# ME433-2021-1.net
KiCad netlist of a schematic drawn in EAGLE
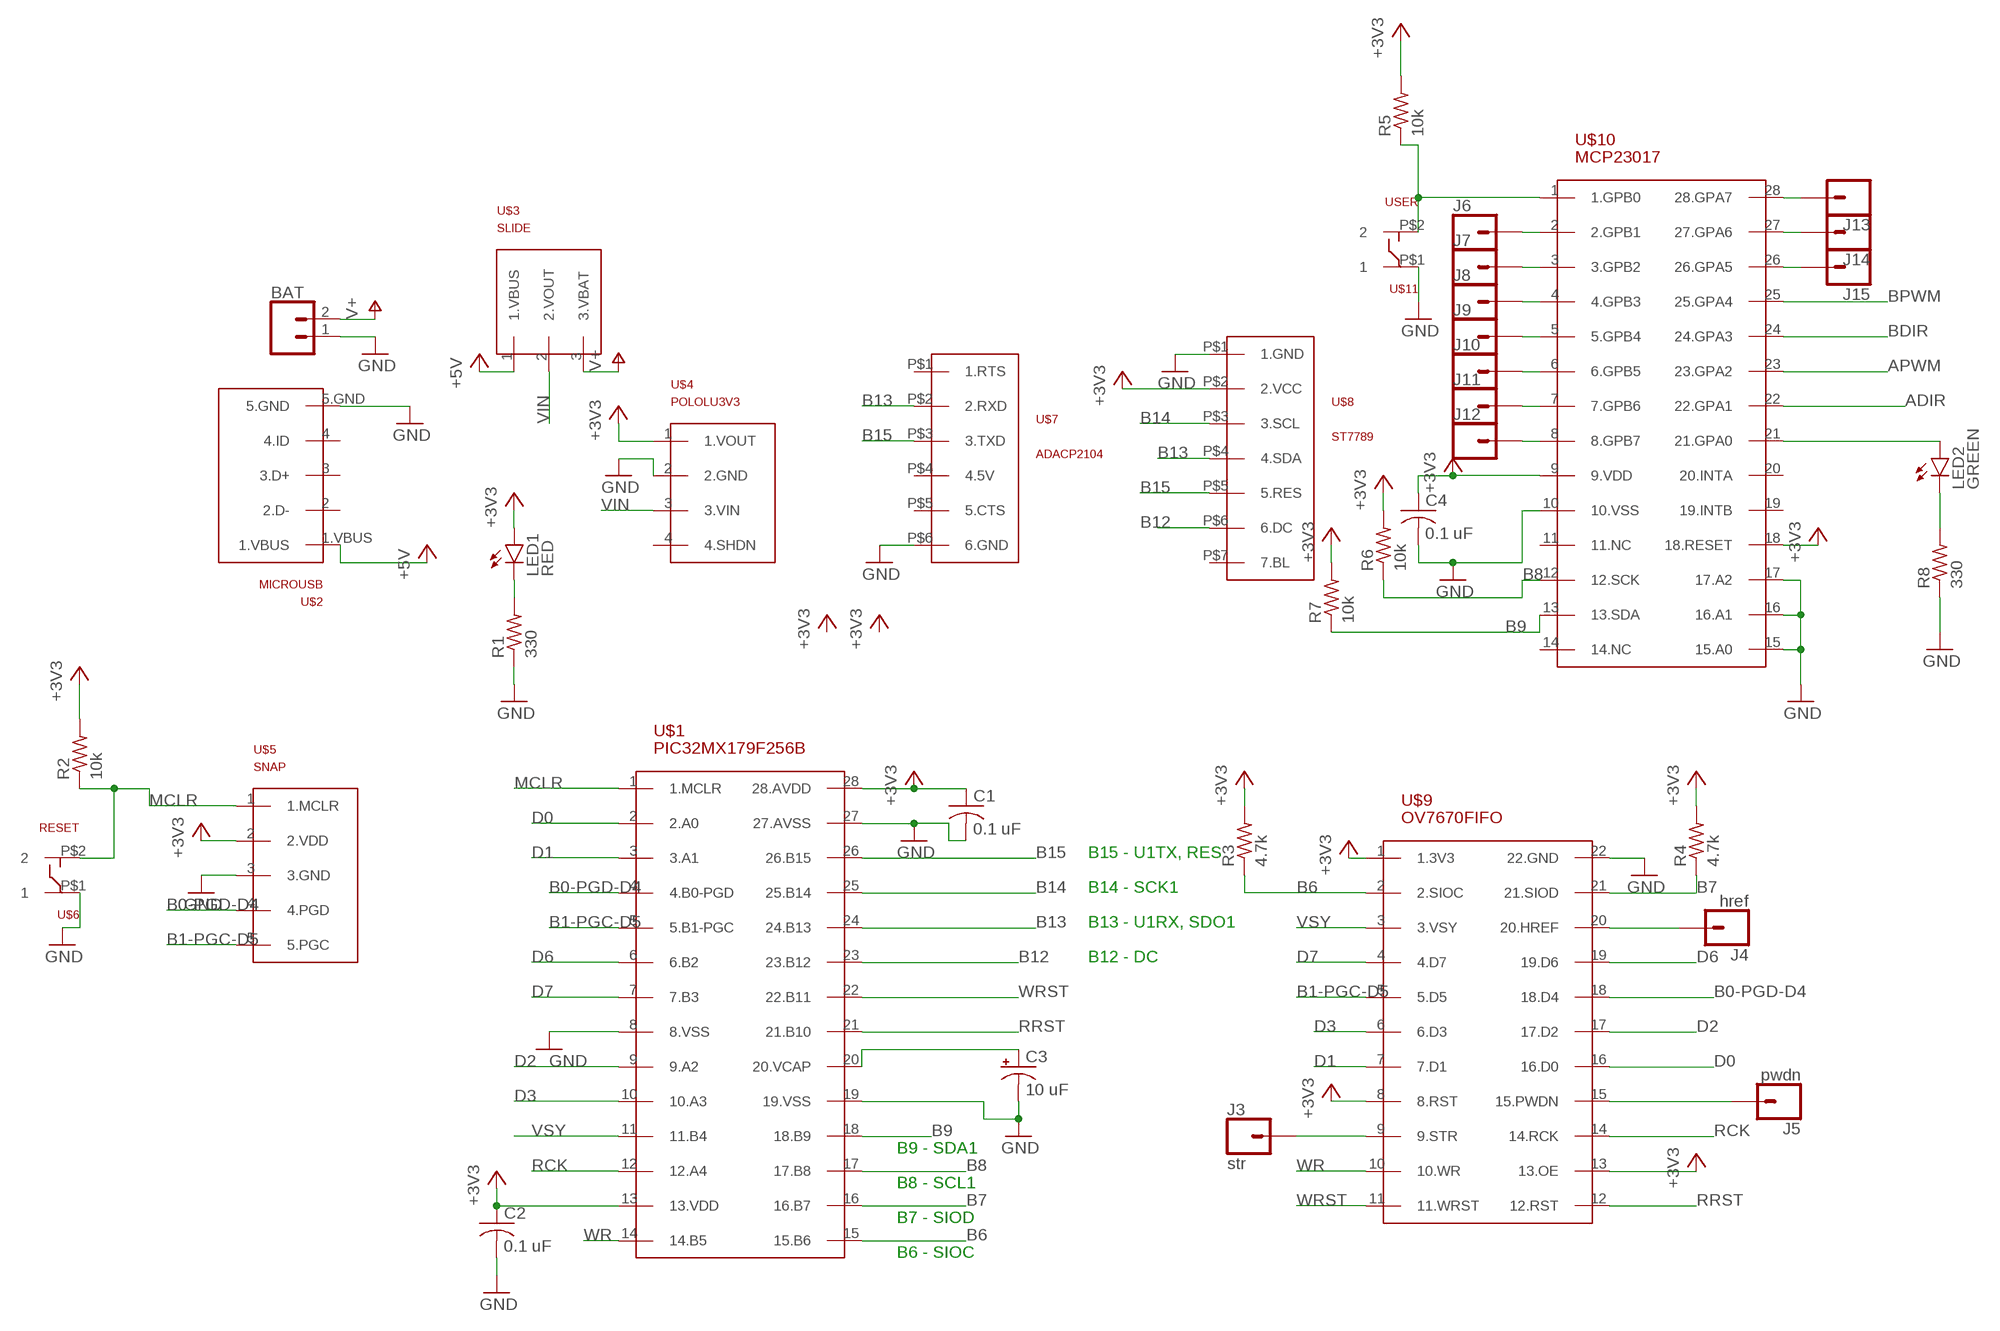
[diagram p0: schematic, sheet 1, part 1 of 2]
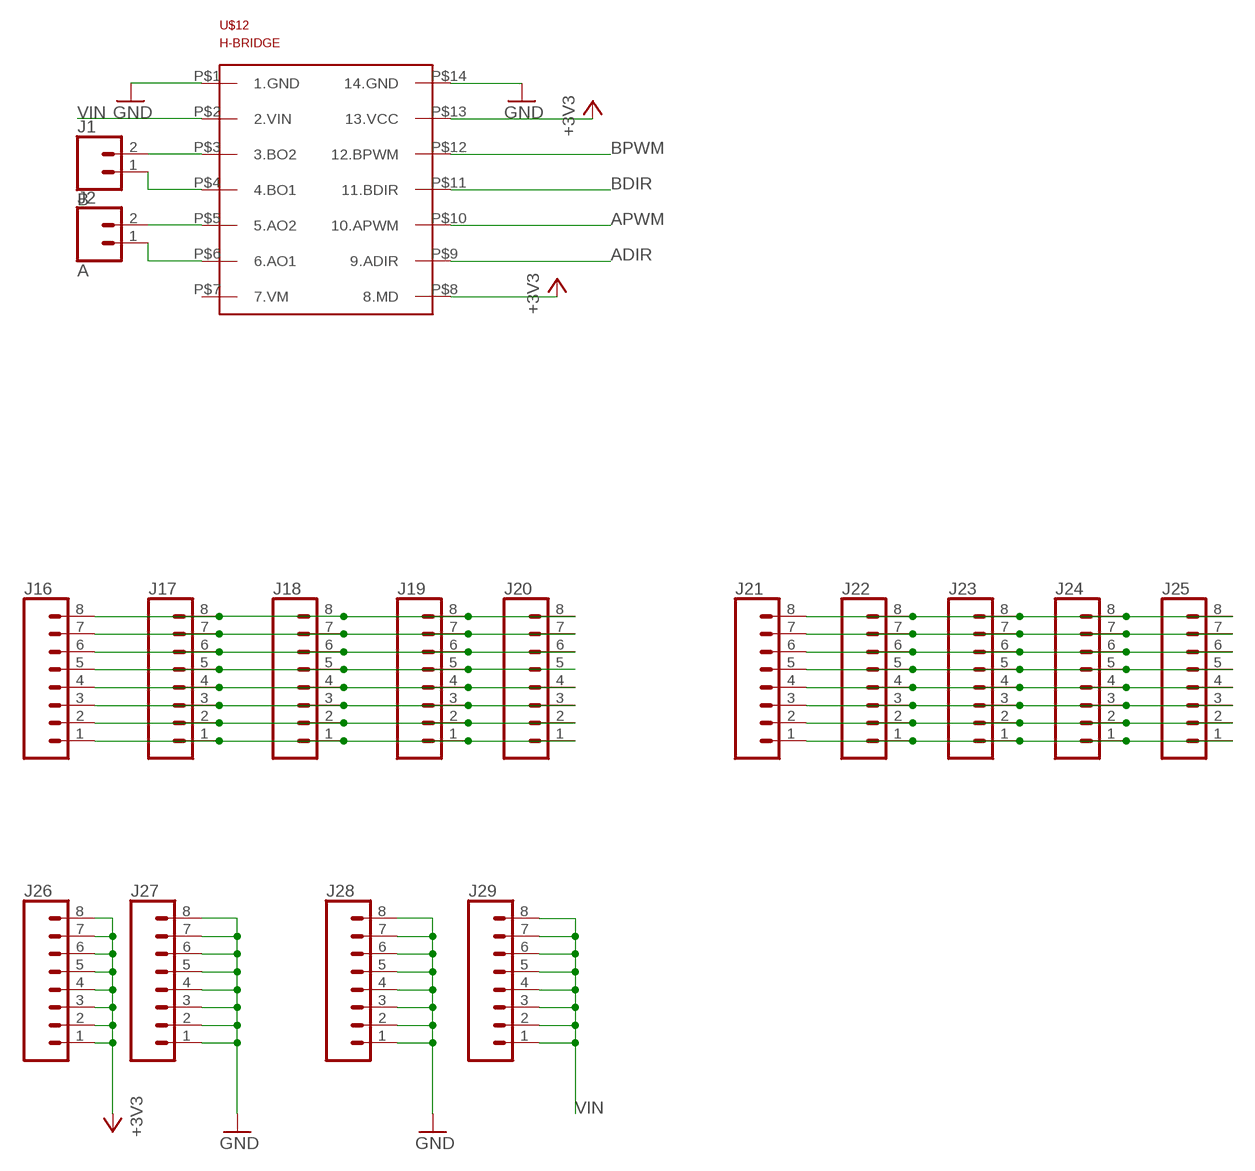
[diagram p1: schematic, sheet 1, part 2 of 2]

(export (version "E")
  (design (tool "Eeschema 10.0.6"))
  (components
    (comp (ref "BAT")
      (value "CONN_02")
      (footprint "eagle-import:1X02")
      (libsource (lib "eagle-import") (part "SparkFun-Connectors_CONN_02"))
    )
    (comp (ref "C1")
      (value "0.1 uF")
      (footprint "eagle-import:C025-030X050")
      (libsource (lib "eagle-import") (part "C-US025-030X050"))
    )
    (comp (ref "C2")
      (value "0.1 uF")
      (footprint "eagle-import:C025-030X050")
      (libsource (lib "eagle-import") (part "C-US025-030X050"))
    )
    (comp (ref "C3")
      (value "10 uF")
      (footprint "eagle-import:B45181B")
      (libsource (lib "eagle-import") (part "CPOL-USB45181B"))
    )
    (comp (ref "C4")
      (value "0.1 uF")
      (footprint "eagle-import:C025-030X050")
      (libsource (lib "eagle-import") (part "C-US025-030X050"))
    )
    (comp (ref "J1")
      (value "B")
      (footprint "eagle-import:1X02")
      (libsource (lib "eagle-import") (part "CONN_02"))
    )
    (comp (ref "J2")
      (value "A")
      (footprint "eagle-import:1X02")
      (libsource (lib "eagle-import") (part "CONN_02"))
    )
    (comp (ref "J3")
      (value "str")
      (footprint "eagle-import:1X01")
      (libsource (lib "eagle-import") (part "CONN_01"))
    )
    (comp (ref "J4")
      (value "href")
      (footprint "eagle-import:1X01")
      (libsource (lib "eagle-import") (part "CONN_01"))
    )
    (comp (ref "J5")
      (value "pwdn")
      (footprint "eagle-import:1X01")
      (libsource (lib "eagle-import") (part "CONN_01"))
    )
    (comp (ref "J6")
      (value "CONN_01")
      (footprint "eagle-import:1X01")
      (libsource (lib "eagle-import") (part "CONN_01"))
    )
    (comp (ref "J7")
      (value "CONN_01")
      (footprint "eagle-import:1X01")
      (libsource (lib "eagle-import") (part "CONN_01"))
    )
    (comp (ref "J8")
      (value "CONN_01")
      (footprint "eagle-import:1X01")
      (libsource (lib "eagle-import") (part "CONN_01"))
    )
    (comp (ref "J9")
      (value "CONN_01")
      (footprint "eagle-import:1X01")
      (libsource (lib "eagle-import") (part "CONN_01"))
    )
    (comp (ref "J10")
      (value "CONN_01")
      (footprint "eagle-import:1X01")
      (libsource (lib "eagle-import") (part "CONN_01"))
    )
    (comp (ref "J11")
      (value "CONN_01")
      (footprint "eagle-import:1X01")
      (libsource (lib "eagle-import") (part "CONN_01"))
    )
    (comp (ref "J12")
      (value "CONN_01")
      (footprint "eagle-import:1X01")
      (libsource (lib "eagle-import") (part "CONN_01"))
    )
    (comp (ref "J13")
      (value "CONN_01")
      (footprint "eagle-import:1X01")
      (libsource (lib "eagle-import") (part "CONN_01"))
    )
    (comp (ref "J14")
      (value "CONN_01")
      (footprint "eagle-import:1X01")
      (libsource (lib "eagle-import") (part "CONN_01"))
    )
    (comp (ref "J15")
      (value "CONN_01")
      (footprint "eagle-import:1X01")
      (libsource (lib "eagle-import") (part "CONN_01"))
    )
    (comp (ref "J16")
      (value "CONN_08\"")
      (footprint "eagle-import:1X08")
      (libsource (lib "eagle-import") (part "CONN_08{dblquote}"))
    )
    (comp (ref "J17")
      (value "CONN_08\"")
      (footprint "eagle-import:1X08")
      (libsource (lib "eagle-import") (part "CONN_08{dblquote}"))
    )
    (comp (ref "J18")
      (value "CONN_08\"")
      (footprint "eagle-import:1X08")
      (libsource (lib "eagle-import") (part "CONN_08{dblquote}"))
    )
    (comp (ref "J19")
      (value "CONN_08\"")
      (footprint "eagle-import:1X08")
      (libsource (lib "eagle-import") (part "CONN_08{dblquote}"))
    )
    (comp (ref "J20")
      (value "CONN_08\"")
      (footprint "eagle-import:1X08")
      (libsource (lib "eagle-import") (part "CONN_08{dblquote}"))
    )
    (comp (ref "J21")
      (value "CONN_08\"")
      (footprint "eagle-import:1X08")
      (libsource (lib "eagle-import") (part "CONN_08{dblquote}"))
    )
    (comp (ref "J22")
      (value "CONN_08\"")
      (footprint "eagle-import:1X08")
      (libsource (lib "eagle-import") (part "CONN_08{dblquote}"))
    )
    (comp (ref "J23")
      (value "CONN_08\"")
      (footprint "eagle-import:1X08")
      (libsource (lib "eagle-import") (part "CONN_08{dblquote}"))
    )
    (comp (ref "J24")
      (value "CONN_08\"")
      (footprint "eagle-import:1X08")
      (libsource (lib "eagle-import") (part "CONN_08{dblquote}"))
    )
    (comp (ref "J25")
      (value "CONN_08\"")
      (footprint "eagle-import:1X08")
      (libsource (lib "eagle-import") (part "CONN_08{dblquote}"))
    )
    (comp (ref "J26")
      (value "CONN_08\"")
      (footprint "eagle-import:1X08")
      (libsource (lib "eagle-import") (part "CONN_08{dblquote}"))
    )
    (comp (ref "J27")
      (value "CONN_08\"")
      (footprint "eagle-import:1X08")
      (libsource (lib "eagle-import") (part "CONN_08{dblquote}"))
    )
    (comp (ref "J28")
      (value "CONN_08\"")
      (footprint "eagle-import:1X08")
      (libsource (lib "eagle-import") (part "CONN_08{dblquote}"))
    )
    (comp (ref "J29")
      (value "CONN_08\"")
      (footprint "eagle-import:1X08")
      (libsource (lib "eagle-import") (part "CONN_08{dblquote}"))
    )
    (comp (ref "LED1")
      (value "RED")
      (footprint "eagle-import:LED3MM")
      (libsource (lib "eagle-import") (part "LED3MM"))
    )
    (comp (ref "LED2")
      (value "GREEN")
      (footprint "eagle-import:LED3MM")
      (libsource (lib "eagle-import") (part "LED3MM"))
    )
    (comp (ref "R1")
      (value "330")
      (footprint "eagle-import:0207_10")
      (libsource (lib "eagle-import") (part "R-US_0207/10"))
    )
    (comp (ref "R2")
      (value "10k")
      (footprint "eagle-import:0207_10")
      (libsource (lib "eagle-import") (part "R-US_0207/10"))
    )
    (comp (ref "R3")
      (value "4.7k")
      (footprint "eagle-import:0207_10")
      (libsource (lib "eagle-import") (part "R-US_0207/10"))
    )
    (comp (ref "R4")
      (value "4.7k")
      (footprint "eagle-import:0207_10")
      (libsource (lib "eagle-import") (part "R-US_0207/10"))
    )
    (comp (ref "R5")
      (value "10k")
      (footprint "eagle-import:0207_10")
      (libsource (lib "eagle-import") (part "R-US_0207/10"))
    )
    (comp (ref "R6")
      (value "10k")
      (footprint "eagle-import:0207_10")
      (libsource (lib "eagle-import") (part "R-US_0207/10"))
    )
    (comp (ref "R7")
      (value "10k")
      (footprint "eagle-import:0207_10")
      (libsource (lib "eagle-import") (part "R-US_0207/10"))
    )
    (comp (ref "R8")
      (value "330")
      (footprint "eagle-import:0207_10")
      (libsource (lib "eagle-import") (part "R-US_0207/10"))
    )
    (comp (ref "U$1")
      (value "PIC32MX179F256B")
      (footprint "eagle-import:DIL28-3")
      (libsource (lib "eagle-import") (part "PIC32MX179F256B"))
    )
    (comp (ref "U$2")
      (value "MICROUSB")
      (footprint "eagle-import:MICROUSB")
      (libsource (lib "eagle-import") (part "MICROUSB"))
    )
    (comp (ref "U$3")
      (value "SLIDE")
      (footprint "eagle-import:SLIDE")
      (libsource (lib "eagle-import") (part "SLIDE"))
    )
    (comp (ref "U$4")
      (value "POLOLU3V3")
      (footprint "eagle-import:POLOLU3V3")
      (libsource (lib "eagle-import") (part "POLOLU3V3"))
    )
    (comp (ref "U$5")
      (value "SNAP")
      (footprint "eagle-import:SNAP")
      (libsource (lib "eagle-import") (part "SNAP"))
    )
    (comp (ref "U$6")
      (value "RESET")
      (footprint "eagle-import:PUSH")
      (libsource (lib "eagle-import") (part "PUSH"))
    )
    (comp (ref "U$7")
      (value "ADACP2104")
      (footprint "eagle-import:ADACP2104")
      (libsource (lib "eagle-import") (part "ADACP2104"))
    )
    (comp (ref "U$8")
      (value "ST7789")
      (footprint "eagle-import:ST7789")
      (libsource (lib "eagle-import") (part "ST7789"))
    )
    (comp (ref "U$9")
      (value "OV7670FIFO")
      (footprint "eagle-import:OV7670FIFO")
      (libsource (lib "eagle-import") (part "OV7670FIFO"))
    )
    (comp (ref "U$10")
      (value "MCP23017")
      (footprint "eagle-import:DIL28-3")
      (libsource (lib "eagle-import") (part "MCP23017"))
    )
    (comp (ref "U$11")
      (value "USER")
      (footprint "eagle-import:PUSH")
      (libsource (lib "eagle-import") (part "PUSH"))
    )
    (comp (ref "U$12")
      (value "H-BRIDGE")
      (footprint "eagle-import:H-BRIDGE")
      (libsource (lib "eagle-import") (part "H-BRIDGE"))
    )
  )
  (nets
    (net (code "1") (name "+3V3") (class "Default")
      (node (ref "C1") (pin "1") (pinfunction "1_1") (pintype "passive"))
      (node (ref "C2") (pin "1") (pinfunction "1_1") (pintype "passive"))
      (node (ref "C4") (pin "1") (pinfunction "1_1") (pintype "passive"))
      (node (ref "J26") (pin "1") (pinfunction "1_1") (pintype "passive"))
      (node (ref "J26") (pin "2") (pinfunction "2_2") (pintype "passive"))
      (node (ref "J26") (pin "3") (pinfunction "3_3") (pintype "passive"))
      (node (ref "J26") (pin "4") (pinfunction "4_4") (pintype "passive"))
      (node (ref "J26") (pin "5") (pinfunction "5_5") (pintype "passive"))
      (node (ref "J26") (pin "6") (pinfunction "6_6") (pintype "passive"))
      (node (ref "J26") (pin "7") (pinfunction "7_7") (pintype "passive"))
      (node (ref "J26") (pin "8") (pinfunction "8_8") (pintype "passive"))
      (node (ref "LED1") (pin "A") (pinfunction "A_A") (pintype "passive"))
      (node (ref "R2") (pin "2") (pinfunction "2_2") (pintype "passive"))
      (node (ref "R3") (pin "2") (pinfunction "2_2") (pintype "passive"))
      (node (ref "R4") (pin "2") (pinfunction "2_2") (pintype "passive"))
      (node (ref "R5") (pin "2") (pinfunction "2_2") (pintype "passive"))
      (node (ref "R6") (pin "2") (pinfunction "2_2") (pintype "passive"))
      (node (ref "R7") (pin "2") (pinfunction "2_2") (pintype "passive"))
      (node (ref "U$1") (pin "13") (pinfunction "13.VDD_13") (pintype "bidirectional"))
      (node (ref "U$1") (pin "28") (pinfunction "28.AVDD_28") (pintype "bidirectional"))
      (node (ref "U$10") (pin "18") (pinfunction "18.RESET_18") (pintype "bidirectional"))
      (node (ref "U$10") (pin "9") (pinfunction "9.VDD_9") (pintype "bidirectional"))
      (node (ref "U$12") (pin "P$13") (pinfunction "13.VCC_P$13") (pintype "bidirectional"))
      (node (ref "U$12") (pin "P$8") (pinfunction "8.MD_P$8") (pintype "bidirectional"))
      (node (ref "U$4") (pin "1") (pinfunction "1.VOUT_1") (pintype "bidirectional"))
      (node (ref "U$5") (pin "2") (pinfunction "2.VDD_2") (pintype "bidirectional"))
      (node (ref "U$8") (pin "P$2") (pinfunction "2.VCC_P$2") (pintype "bidirectional"))
      (node (ref "U$9") (pin "1") (pinfunction "1.3V3_1") (pintype "bidirectional"))
      (node (ref "U$9") (pin "13") (pinfunction "13.OE_13") (pintype "bidirectional"))
      (node (ref "U$9") (pin "8") (pinfunction "8.RST_8") (pintype "bidirectional"))
    )
    (net (code "2") (name "+5V") (class "Default")
      (node (ref "U$2") (pin "1.VBUS") (pinfunction "1.VBUS_1.VBUS") (pintype "bidirectional"))
      (node (ref "U$3") (pin "1") (pinfunction "1.VBUS_1") (pintype "bidirectional"))
    )
    (net (code "3") (name "/ADIR") (class "Default")
      (node (ref "U$10") (pin "22") (pinfunction "22.GPA1_22") (pintype "bidirectional"))
      (node (ref "U$12") (pin "P$9") (pinfunction "9.ADIR_P$9") (pintype "bidirectional"))
    )
    (net (code "4") (name "/APWM") (class "Default")
      (node (ref "U$10") (pin "23") (pinfunction "23.GPA2_23") (pintype "bidirectional"))
      (node (ref "U$12") (pin "P$10") (pinfunction "10.APWM_P$10") (pintype "bidirectional"))
    )
    (net (code "5") (name "/B0-PGD-D4") (class "Default")
      (node (ref "U$1") (pin "4") (pinfunction "4.B0-PGD_4") (pintype "bidirectional"))
      (node (ref "U$5") (pin "4") (pinfunction "4.PGD_4") (pintype "bidirectional"))
      (node (ref "U$9") (pin "18") (pinfunction "18.D4_18") (pintype "bidirectional"))
    )
    (net (code "6") (name "/B1-PGC-D5") (class "Default")
      (node (ref "U$1") (pin "5") (pinfunction "5.B1-PGC_5") (pintype "bidirectional"))
      (node (ref "U$5") (pin "5") (pinfunction "5.PGC_5") (pintype "bidirectional"))
      (node (ref "U$9") (pin "5") (pinfunction "5.D5_5") (pintype "bidirectional"))
    )
    (net (code "7") (name "/B6") (class "Default")
      (node (ref "R3") (pin "1") (pinfunction "1_1") (pintype "passive"))
      (node (ref "U$1") (pin "15") (pinfunction "15.B6_15") (pintype "bidirectional"))
      (node (ref "U$9") (pin "2") (pinfunction "2.SIOC_2") (pintype "bidirectional"))
    )
    (net (code "8") (name "/B7") (class "Default")
      (node (ref "R4") (pin "1") (pinfunction "1_1") (pintype "passive"))
      (node (ref "U$1") (pin "16") (pinfunction "16.B7_16") (pintype "bidirectional"))
      (node (ref "U$9") (pin "21") (pinfunction "21.SIOD_21") (pintype "bidirectional"))
    )
    (net (code "9") (name "/B8") (class "Default")
      (node (ref "R6") (pin "1") (pinfunction "1_1") (pintype "passive"))
      (node (ref "U$1") (pin "17") (pinfunction "17.B8_17") (pintype "bidirectional"))
      (node (ref "U$10") (pin "12") (pinfunction "12.SCK_12") (pintype "bidirectional"))
    )
    (net (code "10") (name "/B9") (class "Default")
      (node (ref "R7") (pin "1") (pinfunction "1_1") (pintype "passive"))
      (node (ref "U$1") (pin "18") (pinfunction "18.B9_18") (pintype "bidirectional"))
      (node (ref "U$10") (pin "13") (pinfunction "13.SDA_13") (pintype "bidirectional"))
    )
    (net (code "11") (name "/B12") (class "Default")
      (node (ref "U$1") (pin "23") (pinfunction "23.B12_23") (pintype "bidirectional"))
      (node (ref "U$8") (pin "P$6") (pinfunction "6.DC_P$6") (pintype "bidirectional"))
    )
    (net (code "12") (name "/B13") (class "Default")
      (node (ref "U$1") (pin "24") (pinfunction "24.B13_24") (pintype "bidirectional"))
      (node (ref "U$7") (pin "P$2") (pinfunction "2.RXD_P$2") (pintype "bidirectional"))
      (node (ref "U$8") (pin "P$4") (pinfunction "4.SDA_P$4") (pintype "bidirectional"))
    )
    (net (code "13") (name "/B14") (class "Default")
      (node (ref "U$1") (pin "25") (pinfunction "25.B14_25") (pintype "bidirectional"))
      (node (ref "U$8") (pin "P$3") (pinfunction "3.SCL_P$3") (pintype "bidirectional"))
    )
    (net (code "14") (name "/B15") (class "Default")
      (node (ref "U$1") (pin "26") (pinfunction "26.B15_26") (pintype "bidirectional"))
      (node (ref "U$7") (pin "P$3") (pinfunction "3.TXD_P$3") (pintype "bidirectional"))
      (node (ref "U$8") (pin "P$5") (pinfunction "5.RES_P$5") (pintype "bidirectional"))
    )
    (net (code "15") (name "/BDIR") (class "Default")
      (node (ref "U$10") (pin "24") (pinfunction "24.GPA3_24") (pintype "bidirectional"))
      (node (ref "U$12") (pin "P$11") (pinfunction "11.BDIR_P$11") (pintype "bidirectional"))
    )
    (net (code "16") (name "/BPWM") (class "Default")
      (node (ref "U$10") (pin "25") (pinfunction "25.GPA4_25") (pintype "bidirectional"))
      (node (ref "U$12") (pin "P$12") (pinfunction "12.BPWM_P$12") (pintype "bidirectional"))
    )
    (net (code "17") (name "/D0") (class "Default")
      (node (ref "U$1") (pin "2") (pinfunction "2.A0_2") (pintype "bidirectional"))
      (node (ref "U$9") (pin "16") (pinfunction "16.D0_16") (pintype "bidirectional"))
    )
    (net (code "18") (name "/D1") (class "Default")
      (node (ref "U$1") (pin "3") (pinfunction "3.A1_3") (pintype "bidirectional"))
      (node (ref "U$9") (pin "7") (pinfunction "7.D1_7") (pintype "bidirectional"))
    )
    (net (code "19") (name "/D2") (class "Default")
      (node (ref "U$1") (pin "9") (pinfunction "9.A2_9") (pintype "bidirectional"))
      (node (ref "U$9") (pin "17") (pinfunction "17.D2_17") (pintype "bidirectional"))
    )
    (net (code "20") (name "/D3") (class "Default")
      (node (ref "U$1") (pin "10") (pinfunction "10.A3_10") (pintype "bidirectional"))
      (node (ref "U$9") (pin "6") (pinfunction "6.D3_6") (pintype "bidirectional"))
    )
    (net (code "21") (name "/D6") (class "Default")
      (node (ref "U$1") (pin "6") (pinfunction "6.B2_6") (pintype "bidirectional"))
      (node (ref "U$9") (pin "19") (pinfunction "19.D6_19") (pintype "bidirectional"))
    )
    (net (code "22") (name "/D7") (class "Default")
      (node (ref "U$1") (pin "7") (pinfunction "7.B3_7") (pintype "bidirectional"))
      (node (ref "U$9") (pin "4") (pinfunction "4.D7_4") (pintype "bidirectional"))
    )
    (net (code "23") (name "/MCLR") (class "Default")
      (node (ref "R2") (pin "1") (pinfunction "1_1") (pintype "passive"))
      (node (ref "U$1") (pin "1") (pinfunction "1.MCLR_1") (pintype "bidirectional"))
      (node (ref "U$5") (pin "1") (pinfunction "1.MCLR_1") (pintype "bidirectional"))
      (node (ref "U$6") (pin "P$2") (pinfunction "2_P$2") (pintype "bidirectional"))
    )
    (net (code "24") (name "/RCK") (class "Default")
      (node (ref "U$1") (pin "12") (pinfunction "12.A4_12") (pintype "bidirectional"))
      (node (ref "U$9") (pin "14") (pinfunction "14.RCK_14") (pintype "bidirectional"))
    )
    (net (code "25") (name "/RRST") (class "Default")
      (node (ref "U$1") (pin "21") (pinfunction "21.B10_21") (pintype "bidirectional"))
      (node (ref "U$9") (pin "12") (pinfunction "12.RST_12") (pintype "bidirectional"))
    )
    (net (code "26") (name "/VIN") (class "Default")
      (node (ref "J29") (pin "1") (pinfunction "1_1") (pintype "passive"))
      (node (ref "J29") (pin "2") (pinfunction "2_2") (pintype "passive"))
      (node (ref "J29") (pin "3") (pinfunction "3_3") (pintype "passive"))
      (node (ref "J29") (pin "4") (pinfunction "4_4") (pintype "passive"))
      (node (ref "J29") (pin "5") (pinfunction "5_5") (pintype "passive"))
      (node (ref "J29") (pin "6") (pinfunction "6_6") (pintype "passive"))
      (node (ref "J29") (pin "7") (pinfunction "7_7") (pintype "passive"))
      (node (ref "J29") (pin "8") (pinfunction "8_8") (pintype "passive"))
      (node (ref "U$12") (pin "P$2") (pinfunction "2.VIN_P$2") (pintype "bidirectional"))
      (node (ref "U$3") (pin "2") (pinfunction "2.VOUT_2") (pintype "bidirectional"))
      (node (ref "U$4") (pin "3") (pinfunction "3.VIN_3") (pintype "bidirectional"))
    )
    (net (code "27") (name "/VSY") (class "Default")
      (node (ref "U$1") (pin "11") (pinfunction "11.B4_11") (pintype "bidirectional"))
      (node (ref "U$9") (pin "3") (pinfunction "3.VSY_3") (pintype "bidirectional"))
    )
    (net (code "28") (name "/WR") (class "Default")
      (node (ref "U$1") (pin "14") (pinfunction "14.B5_14") (pintype "bidirectional"))
      (node (ref "U$9") (pin "10") (pinfunction "10.WR_10") (pintype "bidirectional"))
    )
    (net (code "29") (name "/WRST") (class "Default")
      (node (ref "U$1") (pin "22") (pinfunction "22.B11_22") (pintype "bidirectional"))
      (node (ref "U$9") (pin "11") (pinfunction "11.WRST_11") (pintype "bidirectional"))
    )
    (net (code "30") (name "GND") (class "Default")
      (node (ref "BAT") (pin "1") (pinfunction "1_1") (pintype "passive"))
      (node (ref "C1") (pin "2") (pinfunction "2_2") (pintype "passive"))
      (node (ref "C2") (pin "2") (pinfunction "2_2") (pintype "passive"))
      (node (ref "C3") (pin "-") (pinfunction "-_-") (pintype "passive"))
      (node (ref "C4") (pin "2") (pinfunction "2_2") (pintype "passive"))
      (node (ref "J27") (pin "1") (pinfunction "1_1") (pintype "passive"))
      (node (ref "J27") (pin "2") (pinfunction "2_2") (pintype "passive"))
      (node (ref "J27") (pin "3") (pinfunction "3_3") (pintype "passive"))
      (node (ref "J27") (pin "4") (pinfunction "4_4") (pintype "passive"))
      (node (ref "J27") (pin "5") (pinfunction "5_5") (pintype "passive"))
      (node (ref "J27") (pin "6") (pinfunction "6_6") (pintype "passive"))
      (node (ref "J27") (pin "7") (pinfunction "7_7") (pintype "passive"))
      (node (ref "J27") (pin "8") (pinfunction "8_8") (pintype "passive"))
      (node (ref "J28") (pin "1") (pinfunction "1_1") (pintype "passive"))
      (node (ref "J28") (pin "2") (pinfunction "2_2") (pintype "passive"))
      (node (ref "J28") (pin "3") (pinfunction "3_3") (pintype "passive"))
      (node (ref "J28") (pin "4") (pinfunction "4_4") (pintype "passive"))
      (node (ref "J28") (pin "5") (pinfunction "5_5") (pintype "passive"))
      (node (ref "J28") (pin "6") (pinfunction "6_6") (pintype "passive"))
      (node (ref "J28") (pin "7") (pinfunction "7_7") (pintype "passive"))
      (node (ref "J28") (pin "8") (pinfunction "8_8") (pintype "passive"))
      (node (ref "R1") (pin "1") (pinfunction "1_1") (pintype "passive"))
      (node (ref "R8") (pin "1") (pinfunction "1_1") (pintype "passive"))
      (node (ref "U$1") (pin "19") (pinfunction "19.VSS_19") (pintype "bidirectional"))
      (node (ref "U$1") (pin "27") (pinfunction "27.AVSS_27") (pintype "bidirectional"))
      (node (ref "U$1") (pin "8") (pinfunction "8.VSS_8") (pintype "bidirectional"))
      (node (ref "U$10") (pin "10") (pinfunction "10.VSS_10") (pintype "bidirectional"))
      (node (ref "U$10") (pin "15") (pinfunction "15.A0_15") (pintype "bidirectional"))
      (node (ref "U$10") (pin "16") (pinfunction "16.A1_16") (pintype "bidirectional"))
      (node (ref "U$10") (pin "17") (pinfunction "17.A2_17") (pintype "bidirectional"))
      (node (ref "U$11") (pin "P$1") (pinfunction "1_P$1") (pintype "bidirectional"))
      (node (ref "U$12") (pin "P$1") (pinfunction "1.GND_P$1") (pintype "bidirectional"))
      (node (ref "U$12") (pin "P$14") (pinfunction "14.GND_P$14") (pintype "bidirectional"))
      (node (ref "U$2") (pin "5.GND") (pinfunction "5.GND_5.GND") (pintype "bidirectional"))
      (node (ref "U$4") (pin "2") (pinfunction "2.GND_2") (pintype "bidirectional"))
      (node (ref "U$5") (pin "3") (pinfunction "3.GND_3") (pintype "bidirectional"))
      (node (ref "U$6") (pin "P$1") (pinfunction "1_P$1") (pintype "bidirectional"))
      (node (ref "U$7") (pin "P$6") (pinfunction "6.GND_P$6") (pintype "bidirectional"))
      (node (ref "U$8") (pin "P$1") (pinfunction "1.GND_P$1") (pintype "bidirectional"))
      (node (ref "U$9") (pin "22") (pinfunction "22.GND_22") (pintype "bidirectional"))
    )
    (net (code "31") (name "Net-(J16-Pad1)") (class "Default")
      (node (ref "J16") (pin "1") (pinfunction "1_1") (pintype "passive"))
      (node (ref "J17") (pin "1") (pinfunction "1_1") (pintype "passive"))
      (node (ref "J18") (pin "1") (pinfunction "1_1") (pintype "passive"))
      (node (ref "J19") (pin "1") (pinfunction "1_1") (pintype "passive"))
      (node (ref "J20") (pin "1") (pinfunction "1_1") (pintype "passive"))
    )
    (net (code "32") (name "Net-(J16-Pad2)") (class "Default")
      (node (ref "J16") (pin "2") (pinfunction "2_2") (pintype "passive"))
      (node (ref "J17") (pin "2") (pinfunction "2_2") (pintype "passive"))
      (node (ref "J18") (pin "2") (pinfunction "2_2") (pintype "passive"))
      (node (ref "J19") (pin "2") (pinfunction "2_2") (pintype "passive"))
      (node (ref "J20") (pin "2") (pinfunction "2_2") (pintype "passive"))
    )
    (net (code "33") (name "Net-(J16-Pad3)") (class "Default")
      (node (ref "J16") (pin "3") (pinfunction "3_3") (pintype "passive"))
      (node (ref "J17") (pin "3") (pinfunction "3_3") (pintype "passive"))
      (node (ref "J18") (pin "3") (pinfunction "3_3") (pintype "passive"))
      (node (ref "J19") (pin "3") (pinfunction "3_3") (pintype "passive"))
      (node (ref "J20") (pin "3") (pinfunction "3_3") (pintype "passive"))
    )
    (net (code "34") (name "Net-(J16-Pad4)") (class "Default")
      (node (ref "J16") (pin "4") (pinfunction "4_4") (pintype "passive"))
      (node (ref "J17") (pin "4") (pinfunction "4_4") (pintype "passive"))
      (node (ref "J18") (pin "4") (pinfunction "4_4") (pintype "passive"))
      (node (ref "J19") (pin "4") (pinfunction "4_4") (pintype "passive"))
      (node (ref "J20") (pin "4") (pinfunction "4_4") (pintype "passive"))
    )
    (net (code "35") (name "Net-(J16-Pad5)") (class "Default")
      (node (ref "J16") (pin "5") (pinfunction "5_5") (pintype "passive"))
      (node (ref "J17") (pin "5") (pinfunction "5_5") (pintype "passive"))
      (node (ref "J18") (pin "5") (pinfunction "5_5") (pintype "passive"))
      (node (ref "J19") (pin "5") (pinfunction "5_5") (pintype "passive"))
      (node (ref "J20") (pin "5") (pinfunction "5_5") (pintype "passive"))
    )
    (net (code "36") (name "Net-(J16-Pad6)") (class "Default")
      (node (ref "J16") (pin "6") (pinfunction "6_6") (pintype "passive"))
      (node (ref "J17") (pin "6") (pinfunction "6_6") (pintype "passive"))
      (node (ref "J18") (pin "6") (pinfunction "6_6") (pintype "passive"))
      (node (ref "J19") (pin "6") (pinfunction "6_6") (pintype "passive"))
      (node (ref "J20") (pin "6") (pinfunction "6_6") (pintype "passive"))
    )
    (net (code "37") (name "Net-(J16-Pad7)") (class "Default")
      (node (ref "J16") (pin "7") (pinfunction "7_7") (pintype "passive"))
      (node (ref "J17") (pin "7") (pinfunction "7_7") (pintype "passive"))
      (node (ref "J18") (pin "7") (pinfunction "7_7") (pintype "passive"))
      (node (ref "J19") (pin "7") (pinfunction "7_7") (pintype "passive"))
      (node (ref "J20") (pin "7") (pinfunction "7_7") (pintype "passive"))
    )
    (net (code "38") (name "Net-(J16-Pad8)") (class "Default")
      (node (ref "J16") (pin "8") (pinfunction "8_8") (pintype "passive"))
      (node (ref "J17") (pin "8") (pinfunction "8_8") (pintype "passive"))
      (node (ref "J18") (pin "8") (pinfunction "8_8") (pintype "passive"))
      (node (ref "J19") (pin "8") (pinfunction "8_8") (pintype "passive"))
      (node (ref "J20") (pin "8") (pinfunction "8_8") (pintype "passive"))
    )
    (net (code "39") (name "Net-(J21-Pad1)") (class "Default")
      (node (ref "J21") (pin "1") (pinfunction "1_1") (pintype "passive"))
      (node (ref "J22") (pin "1") (pinfunction "1_1") (pintype "passive"))
      (node (ref "J23") (pin "1") (pinfunction "1_1") (pintype "passive"))
      (node (ref "J24") (pin "1") (pinfunction "1_1") (pintype "passive"))
      (node (ref "J25") (pin "1") (pinfunction "1_1") (pintype "passive"))
    )
    (net (code "40") (name "Net-(J21-Pad2)") (class "Default")
      (node (ref "J21") (pin "2") (pinfunction "2_2") (pintype "passive"))
      (node (ref "J22") (pin "2") (pinfunction "2_2") (pintype "passive"))
      (node (ref "J23") (pin "2") (pinfunction "2_2") (pintype "passive"))
      (node (ref "J24") (pin "2") (pinfunction "2_2") (pintype "passive"))
      (node (ref "J25") (pin "2") (pinfunction "2_2") (pintype "passive"))
    )
    (net (code "41") (name "Net-(J21-Pad3)") (class "Default")
      (node (ref "J21") (pin "3") (pinfunction "3_3") (pintype "passive"))
      (node (ref "J22") (pin "3") (pinfunction "3_3") (pintype "passive"))
      (node (ref "J23") (pin "3") (pinfunction "3_3") (pintype "passive"))
      (node (ref "J24") (pin "3") (pinfunction "3_3") (pintype "passive"))
      (node (ref "J25") (pin "3") (pinfunction "3_3") (pintype "passive"))
    )
    (net (code "42") (name "Net-(J21-Pad4)") (class "Default")
      (node (ref "J21") (pin "4") (pinfunction "4_4") (pintype "passive"))
      (node (ref "J22") (pin "4") (pinfunction "4_4") (pintype "passive"))
      (node (ref "J23") (pin "4") (pinfunction "4_4") (pintype "passive"))
      (node (ref "J24") (pin "4") (pinfunction "4_4") (pintype "passive"))
      (node (ref "J25") (pin "4") (pinfunction "4_4") (pintype "passive"))
    )
    (net (code "43") (name "Net-(J21-Pad5)") (class "Default")
      (node (ref "J21") (pin "5") (pinfunction "5_5") (pintype "passive"))
      (node (ref "J22") (pin "5") (pinfunction "5_5") (pintype "passive"))
      (node (ref "J23") (pin "5") (pinfunction "5_5") (pintype "passive"))
      (node (ref "J24") (pin "5") (pinfunction "5_5") (pintype "passive"))
      (node (ref "J25") (pin "5") (pinfunction "5_5") (pintype "passive"))
    )
    (net (code "44") (name "Net-(J21-Pad6)") (class "Default")
      (node (ref "J21") (pin "6") (pinfunction "6_6") (pintype "passive"))
      (node (ref "J22") (pin "6") (pinfunction "6_6") (pintype "passive"))
      (node (ref "J23") (pin "6") (pinfunction "6_6") (pintype "passive"))
      (node (ref "J24") (pin "6") (pinfunction "6_6") (pintype "passive"))
      (node (ref "J25") (pin "6") (pinfunction "6_6") (pintype "passive"))
    )
    (net (code "45") (name "Net-(J21-Pad7)") (class "Default")
      (node (ref "J21") (pin "7") (pinfunction "7_7") (pintype "passive"))
      (node (ref "J22") (pin "7") (pinfunction "7_7") (pintype "passive"))
      (node (ref "J23") (pin "7") (pinfunction "7_7") (pintype "passive"))
      (node (ref "J24") (pin "7") (pinfunction "7_7") (pintype "passive"))
      (node (ref "J25") (pin "7") (pinfunction "7_7") (pintype "passive"))
    )
    (net (code "46") (name "Net-(J21-Pad8)") (class "Default")
      (node (ref "J21") (pin "8") (pinfunction "8_8") (pintype "passive"))
      (node (ref "J22") (pin "8") (pinfunction "8_8") (pintype "passive"))
      (node (ref "J23") (pin "8") (pinfunction "8_8") (pintype "passive"))
      (node (ref "J24") (pin "8") (pinfunction "8_8") (pintype "passive"))
      (node (ref "J25") (pin "8") (pinfunction "8_8") (pintype "passive"))
    )
    (net (code "47") (name "Net-(LED1-C)") (class "Default")
      (node (ref "LED1") (pin "K") (pinfunction "C_K") (pintype "passive"))
      (node (ref "R1") (pin "2") (pinfunction "2_2") (pintype "passive"))
    )
    (net (code "48") (name "Net-(LED2-C)") (class "Default")
      (node (ref "LED2") (pin "K") (pinfunction "C_K") (pintype "passive"))
      (node (ref "R8") (pin "2") (pinfunction "2_2") (pintype "passive"))
    )
    (net (code "49") (name "Net-(U$1-20.VCAP)") (class "Default")
      (node (ref "C3") (pin "+") (pinfunction "+_+") (pintype "passive"))
      (node (ref "U$1") (pin "20") (pinfunction "20.VCAP_20") (pintype "bidirectional"))
    )
    (net (code "50") (name "Net-(U$9-9.STR)") (class "Default")
      (node (ref "J3") (pin "1") (pinfunction "1_1") (pintype "passive"))
      (node (ref "U$9") (pin "9") (pinfunction "9.STR_9") (pintype "bidirectional"))
    )
    (net (code "51") (name "Net-(U$9-15.PWDN)") (class "Default")
      (node (ref "J5") (pin "1") (pinfunction "1_1") (pintype "passive"))
      (node (ref "U$9") (pin "15") (pinfunction "15.PWDN_15") (pintype "bidirectional"))
    )
    (net (code "52") (name "Net-(U$9-20.HREF)") (class "Default")
      (node (ref "J4") (pin "1") (pinfunction "1_1") (pintype "passive"))
      (node (ref "U$9") (pin "20") (pinfunction "20.HREF_20") (pintype "bidirectional"))
    )
    (net (code "53") (name "Net-(U$10-1.GPB0)") (class "Default")
      (node (ref "R5") (pin "1") (pinfunction "1_1") (pintype "passive"))
      (node (ref "U$10") (pin "1") (pinfunction "1.GPB0_1") (pintype "bidirectional"))
      (node (ref "U$11") (pin "P$2") (pinfunction "2_P$2") (pintype "bidirectional"))
    )
    (net (code "54") (name "Net-(U$10-2.GPB1)") (class "Default")
      (node (ref "J6") (pin "1") (pinfunction "1_1") (pintype "passive"))
      (node (ref "U$10") (pin "2") (pinfunction "2.GPB1_2") (pintype "bidirectional"))
    )
    (net (code "55") (name "Net-(U$10-3.GPB2)") (class "Default")
      (node (ref "J7") (pin "1") (pinfunction "1_1") (pintype "passive"))
      (node (ref "U$10") (pin "3") (pinfunction "3.GPB2_3") (pintype "bidirectional"))
    )
    (net (code "56") (name "Net-(U$10-4.GPB3)") (class "Default")
      (node (ref "J8") (pin "1") (pinfunction "1_1") (pintype "passive"))
      (node (ref "U$10") (pin "4") (pinfunction "4.GPB3_4") (pintype "bidirectional"))
    )
    (net (code "57") (name "Net-(U$10-5.GPB4)") (class "Default")
      (node (ref "J9") (pin "1") (pinfunction "1_1") (pintype "passive"))
      (node (ref "U$10") (pin "5") (pinfunction "5.GPB4_5") (pintype "bidirectional"))
    )
    (net (code "58") (name "Net-(U$10-6.GPB5)") (class "Default")
      (node (ref "J10") (pin "1") (pinfunction "1_1") (pintype "passive"))
      (node (ref "U$10") (pin "6") (pinfunction "6.GPB5_6") (pintype "bidirectional"))
    )
    (net (code "59") (name "Net-(U$10-7.GPB6)") (class "Default")
      (node (ref "J11") (pin "1") (pinfunction "1_1") (pintype "passive"))
      (node (ref "U$10") (pin "7") (pinfunction "7.GPB6_7") (pintype "bidirectional"))
    )
    (net (code "60") (name "Net-(U$10-8.GPB7)") (class "Default")
      (node (ref "J12") (pin "1") (pinfunction "1_1") (pintype "passive"))
      (node (ref "U$10") (pin "8") (pinfunction "8.GPB7_8") (pintype "bidirectional"))
    )
    (net (code "61") (name "Net-(U$10-21.GPA0)") (class "Default")
      (node (ref "LED2") (pin "A") (pinfunction "A_A") (pintype "passive"))
      (node (ref "U$10") (pin "21") (pinfunction "21.GPA0_21") (pintype "bidirectional"))
    )
    (net (code "62") (name "Net-(U$10-26.GPA5)") (class "Default")
      (node (ref "J15") (pin "1") (pinfunction "1_1") (pintype "passive"))
      (node (ref "U$10") (pin "26") (pinfunction "26.GPA5_26") (pintype "bidirectional"))
    )
    (net (code "63") (name "Net-(U$10-27.GPA6)") (class "Default")
      (node (ref "J14") (pin "1") (pinfunction "1_1") (pintype "passive"))
      (node (ref "U$10") (pin "27") (pinfunction "27.GPA6_27") (pintype "bidirectional"))
    )
    (net (code "64") (name "Net-(U$10-28.GPA7)") (class "Default")
      (node (ref "J13") (pin "1") (pinfunction "1_1") (pintype "passive"))
      (node (ref "U$10") (pin "28") (pinfunction "28.GPA7_28") (pintype "bidirectional"))
    )
    (net (code "65") (name "Net-(U$12-3.BO2)") (class "Default")
      (node (ref "J1") (pin "2") (pinfunction "2_2") (pintype "passive"))
      (node (ref "U$12") (pin "P$3") (pinfunction "3.BO2_P$3") (pintype "bidirectional"))
    )
    (net (code "66") (name "Net-(U$12-4.BO1)") (class "Default")
      (node (ref "J1") (pin "1") (pinfunction "1_1") (pintype "passive"))
      (node (ref "U$12") (pin "P$4") (pinfunction "4.BO1_P$4") (pintype "bidirectional"))
    )
    (net (code "67") (name "Net-(U$12-5.AO2)") (class "Default")
      (node (ref "J2") (pin "2") (pinfunction "2_2") (pintype "passive"))
      (node (ref "U$12") (pin "P$5") (pinfunction "5.AO2_P$5") (pintype "bidirectional"))
    )
    (net (code "68") (name "Net-(U$12-6.AO1)") (class "Default")
      (node (ref "J2") (pin "1") (pinfunction "1_1") (pintype "passive"))
      (node (ref "U$12") (pin "P$6") (pinfunction "6.AO1_P$6") (pintype "bidirectional"))
    )
    (net (code "69") (name "V+") (class "Default")
      (node (ref "BAT") (pin "2") (pinfunction "2_2") (pintype "passive"))
      (node (ref "U$3") (pin "3") (pinfunction "3.VBAT_3") (pintype "bidirectional"))
    )
    (net (code "70") (name "unconnected-(U$2-2.D--Pad2)") (class "Default")
      (node (ref "U$2") (pin "2") (pinfunction "2.D-_2") (pintype "bidirectional"))
    )
    (net (code "71") (name "unconnected-(U$2-3.D+-Pad3)") (class "Default")
      (node (ref "U$2") (pin "3") (pinfunction "3.D+_3") (pintype "bidirectional"))
    )
    (net (code "72") (name "unconnected-(U$2-4.ID-Pad4)") (class "Default")
      (node (ref "U$2") (pin "4") (pinfunction "4.ID_4") (pintype "bidirectional"))
    )
    (net (code "73") (name "unconnected-(U$4-4.SHDN-Pad4)") (class "Default")
      (node (ref "U$4") (pin "4") (pinfunction "4.SHDN_4") (pintype "bidirectional"))
    )
    (net (code "74") (name "unconnected-(U$7-1.RTS-PadP$1)") (class "Default")
      (node (ref "U$7") (pin "P$1") (pinfunction "1.RTS_P$1") (pintype "bidirectional"))
    )
    (net (code "75") (name "unconnected-(U$7-4.5V-PadP$4)") (class "Default")
      (node (ref "U$7") (pin "P$4") (pinfunction "4.5V_P$4") (pintype "bidirectional"))
    )
    (net (code "76") (name "unconnected-(U$7-5.CTS-PadP$5)") (class "Default")
      (node (ref "U$7") (pin "P$5") (pinfunction "5.CTS_P$5") (pintype "bidirectional"))
    )
    (net (code "77") (name "unconnected-(U$8-7.BL-PadP$7)") (class "Default")
      (node (ref "U$8") (pin "P$7") (pinfunction "7.BL_P$7") (pintype "bidirectional"))
    )
    (net (code "78") (name "unconnected-(U$10-11.NC-Pad11)") (class "Default")
      (node (ref "U$10") (pin "11") (pinfunction "11.NC_11") (pintype "bidirectional"))
    )
    (net (code "79") (name "unconnected-(U$10-14.NC-Pad14)") (class "Default")
      (node (ref "U$10") (pin "14") (pinfunction "14.NC_14") (pintype "bidirectional"))
    )
    (net (code "80") (name "unconnected-(U$10-19.INTB-Pad19)") (class "Default")
      (node (ref "U$10") (pin "19") (pinfunction "19.INTB_19") (pintype "bidirectional"))
    )
    (net (code "81") (name "unconnected-(U$10-20.INTA-Pad20)") (class "Default")
      (node (ref "U$10") (pin "20") (pinfunction "20.INTA_20") (pintype "bidirectional"))
    )
    (net (code "82") (name "unconnected-(U$12-7.VM-PadP$7)") (class "Default")
      (node (ref "U$12") (pin "P$7") (pinfunction "7.VM_P$7") (pintype "bidirectional"))
    )
  )
)
